# prog_adapter.net
KiCad netlist of a schematic drawn in EAGLE
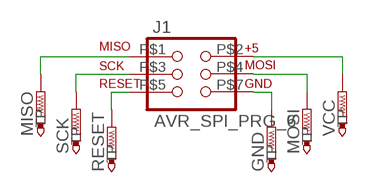
[diagram p0: schematic, sheet 1]

(export (version "E")
  (design (tool "Eeschema 10.0.6"))
  (components
    (comp (ref "GND")
      (value "PTR1PAD1-17")
      (footprint "eagle-import:P1-17")
      (libsource (lib "eagle-import") (part "PTR1PAD1-17"))
    )
    (comp (ref "J1")
      (value "AVR_SPI_PRG_6")
      (footprint "eagle-import:2X3_ICSP_SMD")
      (libsource (lib "eagle-import") (part "AVR_SPI_PRG_6"))
    )
    (comp (ref "MISO")
      (value "PTR1PAD1-17")
      (footprint "eagle-import:P1-17")
      (libsource (lib "eagle-import") (part "PTR1PAD1-17"))
    )
    (comp (ref "MOSI")
      (value "PTR1PAD1-17")
      (footprint "eagle-import:P1-17")
      (libsource (lib "eagle-import") (part "PTR1PAD1-17"))
    )
    (comp (ref "RESET")
      (value "PTR1PAD1-17")
      (footprint "eagle-import:P1-17")
      (libsource (lib "eagle-import") (part "PTR1PAD1-17"))
    )
    (comp (ref "SCK")
      (value "PTR1PAD1-17")
      (footprint "eagle-import:P1-17")
      (libsource (lib "eagle-import") (part "PTR1PAD1-17"))
    )
    (comp (ref "VCC")
      (value "PTR1PAD1-17")
      (footprint "eagle-import:P1-17")
      (libsource (lib "eagle-import") (part "PTR1PAD1-17"))
    )
  )
  (nets
    (net (code "1") (name "Net-(J1-1)") (class "Default")
      (node (ref "J1") (pin "P$1") (pinfunction "1_P$1") (pintype "passive"))
      (node (ref "MISO") (pin "TP") (pinfunction "TP_TP") (pintype "input"))
    )
    (net (code "2") (name "Net-(J1-2)") (class "Default")
      (node (ref "J1") (pin "P$2") (pinfunction "2_P$2") (pintype "passive"))
      (node (ref "VCC") (pin "TP") (pinfunction "TP_TP") (pintype "input"))
    )
    (net (code "3") (name "Net-(J1-3)") (class "Default")
      (node (ref "J1") (pin "P$3") (pinfunction "3_P$3") (pintype "passive"))
      (node (ref "SCK") (pin "TP") (pinfunction "TP_TP") (pintype "input"))
    )
    (net (code "4") (name "Net-(J1-4)") (class "Default")
      (node (ref "J1") (pin "P$4") (pinfunction "4_P$4") (pintype "passive"))
      (node (ref "MOSI") (pin "TP") (pinfunction "TP_TP") (pintype "input"))
    )
    (net (code "5") (name "Net-(J1-5)") (class "Default")
      (node (ref "J1") (pin "P$5") (pinfunction "5_P$5") (pintype "passive"))
      (node (ref "RESET") (pin "TP") (pinfunction "TP_TP") (pintype "input"))
    )
    (net (code "6") (name "Net-(J1-6)") (class "Default")
      (node (ref "GND") (pin "TP") (pinfunction "TP_TP") (pintype "input"))
      (node (ref "J1") (pin "P$7") (pinfunction "6_P$7") (pintype "passive"))
    )
  )
)
